# Sequei_board2.net
KiCad netlist of a schematic drawn in EAGLE
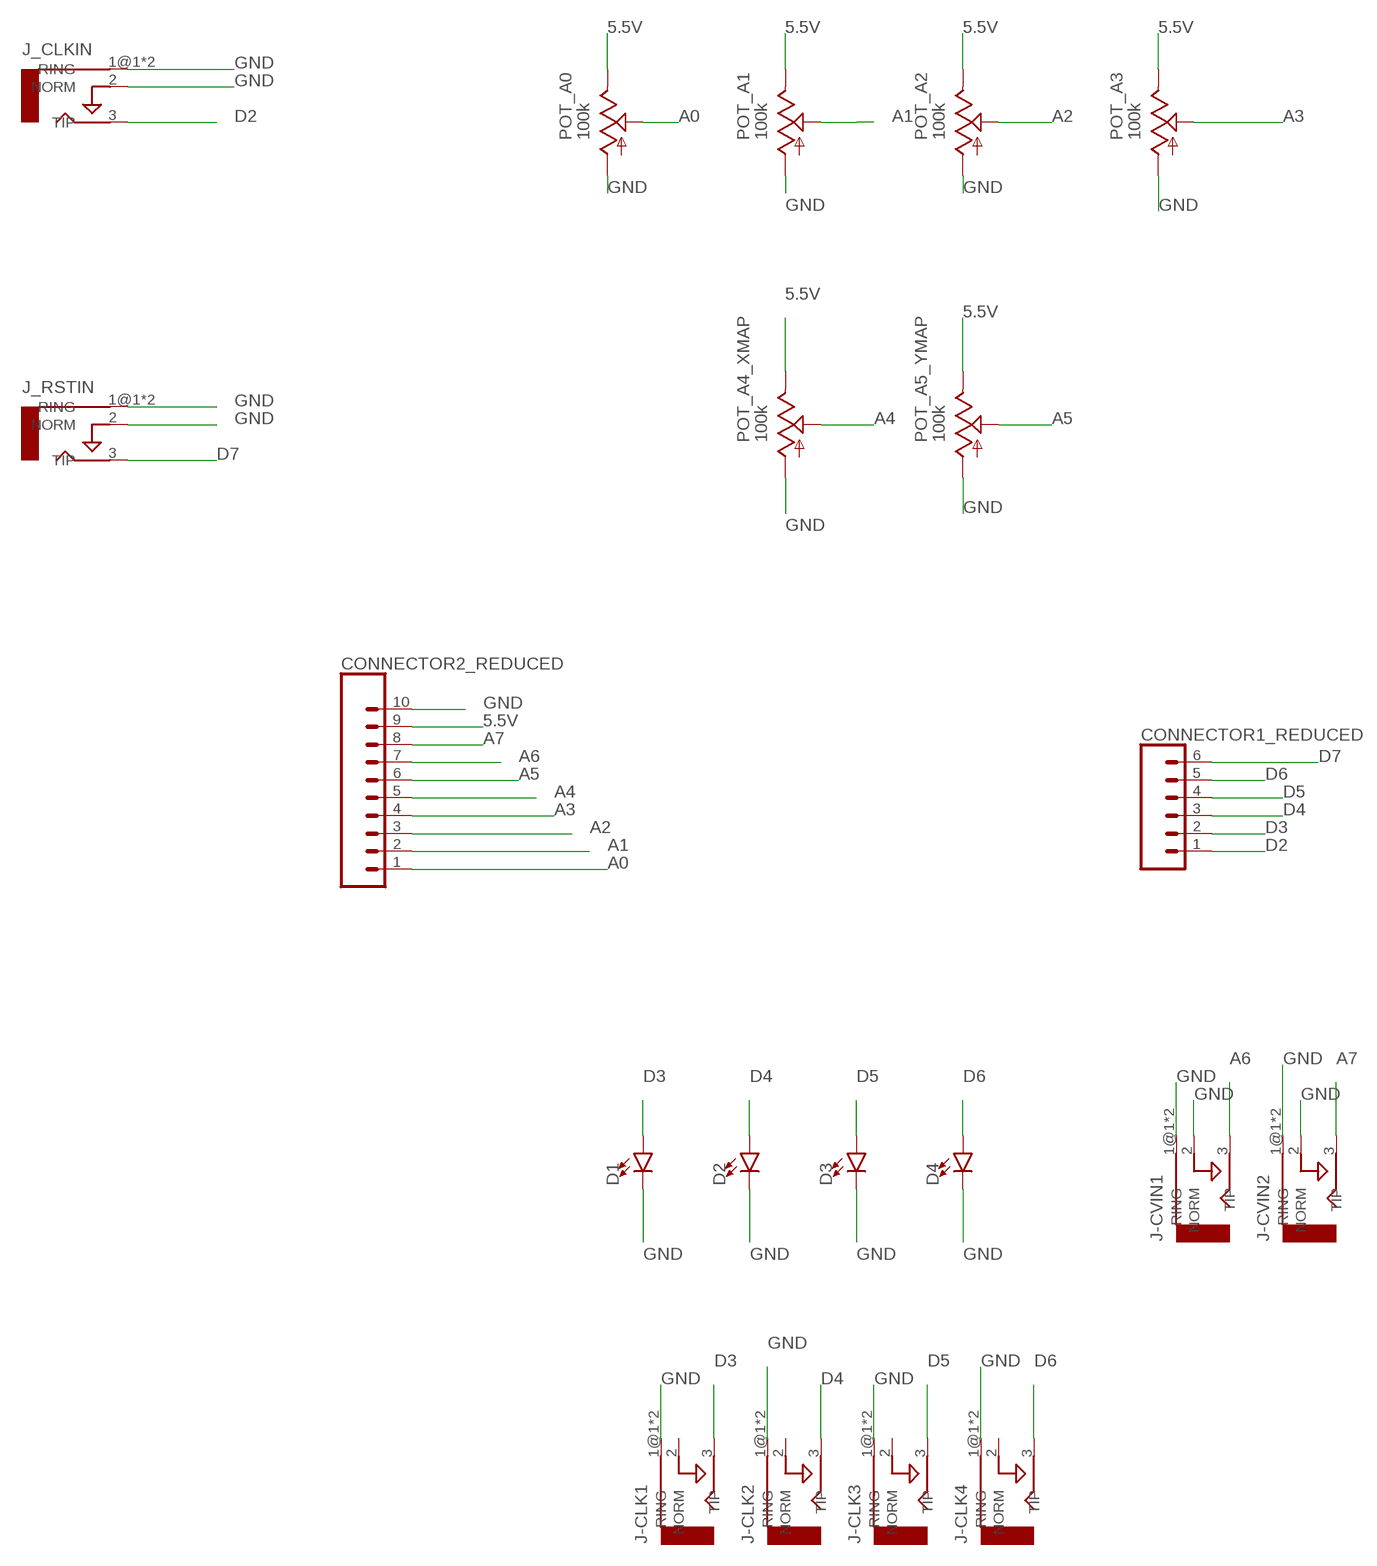
[diagram p0: schematic, sheet 1]

(export (version "E")
  (design (tool "Eeschema 10.0.6"))
  (components
    (comp (ref "CONNECTOR1_REDUCED")
      (value "CONN_06LONGPADS")
      (footprint "eagle-import:1X06_LONGPADS")
      (libsource (lib "eagle-import") (part "CONN_06LONGPADS"))
    )
    (comp (ref "CONNECTOR2_REDUCED")
      (value "CONN_10_LONGPADS10_LONGPADS")
      (footprint "eagle-import:1X10_LONGPADS")
      (libsource (lib "eagle-import") (part "CONN_10_LONGPADS10_LONGPADS"))
    )
    (comp (ref "D1")
      (value "LED-3MM-NO_SILK")
      (footprint "eagle-import:LED_3MM-NS")
      (libsource (lib "eagle-import") (part "LED-3MM-NO_SILK"))
    )
    (comp (ref "D2")
      (value "LED-3MM-NO_SILK")
      (footprint "eagle-import:LED_3MM-NS")
      (libsource (lib "eagle-import") (part "LED-3MM-NO_SILK"))
    )
    (comp (ref "D3")
      (value "LED-3MM-NO_SILK")
      (footprint "eagle-import:LED_3MM-NS")
      (libsource (lib "eagle-import") (part "LED-3MM-NO_SILK"))
    )
    (comp (ref "D4")
      (value "LED-3MM-NO_SILK")
      (footprint "eagle-import:LED_3MM-NS")
      (libsource (lib "eagle-import") (part "LED-3MM-NO_SILK"))
    )
    (comp (ref "J-CLK1")
      (value "AUDIO-JACKERTHENVAR")
      (footprint "eagle-import:ERTHENVAR-JACK")
      (libsource (lib "eagle-import") (part "AUDIO-JACKERTHENVAR"))
    )
    (comp (ref "J-CLK2")
      (value "AUDIO-JACKERTHENVAR")
      (footprint "eagle-import:ERTHENVAR-JACK")
      (libsource (lib "eagle-import") (part "AUDIO-JACKERTHENVAR"))
    )
    (comp (ref "J-CLK3")
      (value "AUDIO-JACKERTHENVAR")
      (footprint "eagle-import:ERTHENVAR-JACK")
      (libsource (lib "eagle-import") (part "AUDIO-JACKERTHENVAR"))
    )
    (comp (ref "J-CLK4")
      (value "AUDIO-JACKERTHENVAR")
      (footprint "eagle-import:ERTHENVAR-JACK")
      (libsource (lib "eagle-import") (part "AUDIO-JACKERTHENVAR"))
    )
    (comp (ref "J-CVIN1")
      (value "AUDIO-JACKERTHENVAR")
      (footprint "eagle-import:ERTHENVAR-JACK")
      (libsource (lib "eagle-import") (part "AUDIO-JACKERTHENVAR"))
    )
    (comp (ref "J-CVIN2")
      (value "AUDIO-JACKERTHENVAR")
      (footprint "eagle-import:ERTHENVAR-JACK")
      (libsource (lib "eagle-import") (part "AUDIO-JACKERTHENVAR"))
    )
    (comp (ref "J_CLKIN")
      (value "AUDIO-JACKERTHENVAR")
      (footprint "eagle-import:ERTHENVAR-JACK")
      (libsource (lib "eagle-import") (part "AUDIO-JACKERTHENVAR"))
    )
    (comp (ref "J_RSTIN")
      (value "AUDIO-JACKERTHENVAR")
      (footprint "eagle-import:ERTHENVAR-JACK")
      (libsource (lib "eagle-import") (part "AUDIO-JACKERTHENVAR"))
    )
    (comp (ref "POT_A0")
      (value "100k")
      (footprint "eagle-import:9MM_SNAP-IN_POT")
      (libsource (lib "eagle-import") (part "9MM_SNAP-IN_POT_"))
    )
    (comp (ref "POT_A1")
      (value "100k")
      (footprint "eagle-import:9MM_SNAP-IN_POT")
      (libsource (lib "eagle-import") (part "9MM_SNAP-IN_POT_"))
    )
    (comp (ref "POT_A2")
      (value "100k")
      (footprint "eagle-import:9MM_SNAP-IN_POT")
      (libsource (lib "eagle-import") (part "9MM_SNAP-IN_POT_"))
    )
    (comp (ref "POT_A3")
      (value "100k")
      (footprint "eagle-import:9MM_SNAP-IN_POT")
      (libsource (lib "eagle-import") (part "9MM_SNAP-IN_POT_"))
    )
    (comp (ref "POT_A4_XMAP")
      (value "100k")
      (footprint "eagle-import:9MM_SNAP-IN_POT")
      (libsource (lib "eagle-import") (part "9MM_SNAP-IN_POT_"))
    )
    (comp (ref "POT_A5_YMAP")
      (value "100k")
      (footprint "eagle-import:9MM_SNAP-IN_POT")
      (libsource (lib "eagle-import") (part "9MM_SNAP-IN_POT_"))
    )
  )
  (nets
    (net (code "1") (name "/5.5V") (class "Default")
      (node (ref "CONNECTOR2_REDUCED") (pin "9") (pinfunction "9_9") (pintype "passive"))
      (node (ref "POT_A0") (pin "3") (pinfunction "E_3") (pintype "passive"))
      (node (ref "POT_A1") (pin "3") (pinfunction "E_3") (pintype "passive"))
      (node (ref "POT_A2") (pin "3") (pinfunction "E_3") (pintype "passive"))
      (node (ref "POT_A3") (pin "3") (pinfunction "E_3") (pintype "passive"))
      (node (ref "POT_A4_XMAP") (pin "3") (pinfunction "E_3") (pintype "passive"))
      (node (ref "POT_A5_YMAP") (pin "3") (pinfunction "E_3") (pintype "passive"))
    )
    (net (code "2") (name "/A0") (class "Default")
      (node (ref "CONNECTOR2_REDUCED") (pin "1") (pinfunction "1_1") (pintype "passive"))
      (node (ref "POT_A0") (pin "2") (pinfunction "S_2") (pintype "passive"))
    )
    (net (code "3") (name "/A1") (class "Default")
      (node (ref "CONNECTOR2_REDUCED") (pin "2") (pinfunction "2_2") (pintype "passive"))
      (node (ref "POT_A1") (pin "2") (pinfunction "S_2") (pintype "passive"))
    )
    (net (code "4") (name "/A2") (class "Default")
      (node (ref "CONNECTOR2_REDUCED") (pin "3") (pinfunction "3_3") (pintype "passive"))
      (node (ref "POT_A2") (pin "2") (pinfunction "S_2") (pintype "passive"))
    )
    (net (code "5") (name "/A3") (class "Default")
      (node (ref "CONNECTOR2_REDUCED") (pin "4") (pinfunction "4_4") (pintype "passive"))
      (node (ref "POT_A3") (pin "2") (pinfunction "S_2") (pintype "passive"))
    )
    (net (code "6") (name "/A4") (class "Default")
      (node (ref "CONNECTOR2_REDUCED") (pin "5") (pinfunction "5_5") (pintype "passive"))
      (node (ref "POT_A4_XMAP") (pin "2") (pinfunction "S_2") (pintype "passive"))
    )
    (net (code "7") (name "/A5") (class "Default")
      (node (ref "CONNECTOR2_REDUCED") (pin "6") (pinfunction "6_6") (pintype "passive"))
      (node (ref "POT_A5_YMAP") (pin "2") (pinfunction "S_2") (pintype "passive"))
    )
    (net (code "8") (name "/A6") (class "Default")
      (node (ref "CONNECTOR2_REDUCED") (pin "7") (pinfunction "7_7") (pintype "passive"))
      (node (ref "J-CVIN1") (pin "3") (pinfunction "TIP_3") (pintype "bidirectional"))
    )
    (net (code "9") (name "/A7") (class "Default")
      (node (ref "CONNECTOR2_REDUCED") (pin "8") (pinfunction "8_8") (pintype "passive"))
      (node (ref "J-CVIN2") (pin "3") (pinfunction "TIP_3") (pintype "bidirectional"))
    )
    (net (code "10") (name "/D2") (class "Default")
      (node (ref "CONNECTOR1_REDUCED") (pin "1") (pinfunction "1_1") (pintype "passive"))
      (node (ref "J_CLKIN") (pin "3") (pinfunction "TIP_3") (pintype "bidirectional"))
    )
    (net (code "11") (name "/D3") (class "Default")
      (node (ref "CONNECTOR1_REDUCED") (pin "2") (pinfunction "2_2") (pintype "passive"))
      (node (ref "D1") (pin "A") (pinfunction "A_A") (pintype "passive"))
      (node (ref "J-CLK1") (pin "3") (pinfunction "TIP_3") (pintype "bidirectional"))
    )
    (net (code "12") (name "/D4") (class "Default")
      (node (ref "CONNECTOR1_REDUCED") (pin "3") (pinfunction "3_3") (pintype "passive"))
      (node (ref "D2") (pin "A") (pinfunction "A_A") (pintype "passive"))
      (node (ref "J-CLK2") (pin "3") (pinfunction "TIP_3") (pintype "bidirectional"))
    )
    (net (code "13") (name "/D5") (class "Default")
      (node (ref "CONNECTOR1_REDUCED") (pin "4") (pinfunction "4_4") (pintype "passive"))
      (node (ref "D3") (pin "A") (pinfunction "A_A") (pintype "passive"))
      (node (ref "J-CLK3") (pin "3") (pinfunction "TIP_3") (pintype "bidirectional"))
    )
    (net (code "14") (name "/D6") (class "Default")
      (node (ref "CONNECTOR1_REDUCED") (pin "5") (pinfunction "5_5") (pintype "passive"))
      (node (ref "D4") (pin "A") (pinfunction "A_A") (pintype "passive"))
      (node (ref "J-CLK4") (pin "3") (pinfunction "TIP_3") (pintype "bidirectional"))
    )
    (net (code "15") (name "/D7") (class "Default")
      (node (ref "CONNECTOR1_REDUCED") (pin "6") (pinfunction "6_6") (pintype "passive"))
      (node (ref "J_RSTIN") (pin "3") (pinfunction "TIP_3") (pintype "bidirectional"))
    )
    (net (code "16") (name "/GND") (class "Default")
      (node (ref "CONNECTOR2_REDUCED") (pin "10") (pinfunction "10_10") (pintype "passive"))
      (node (ref "D1") (pin "K") (pinfunction "C_K") (pintype "passive"))
      (node (ref "D2") (pin "K") (pinfunction "C_K") (pintype "passive"))
      (node (ref "D3") (pin "K") (pinfunction "C_K") (pintype "passive"))
      (node (ref "D4") (pin "K") (pinfunction "C_K") (pintype "passive"))
      (node (ref "J-CLK1") (pin "1@1") (pinfunction "RING_1@1") (pintype "bidirectional"))
      (node (ref "J-CLK1") (pin "1@2") (pinfunction "RING_1@2") (pintype "bidirectional"))
      (node (ref "J-CLK2") (pin "1@1") (pinfunction "RING_1@1") (pintype "bidirectional"))
      (node (ref "J-CLK2") (pin "1@2") (pinfunction "RING_1@2") (pintype "bidirectional"))
      (node (ref "J-CLK3") (pin "1@1") (pinfunction "RING_1@1") (pintype "bidirectional"))
      (node (ref "J-CLK3") (pin "1@2") (pinfunction "RING_1@2") (pintype "bidirectional"))
      (node (ref "J-CLK4") (pin "1@1") (pinfunction "RING_1@1") (pintype "bidirectional"))
      (node (ref "J-CLK4") (pin "1@2") (pinfunction "RING_1@2") (pintype "bidirectional"))
      (node (ref "J-CVIN1") (pin "1@1") (pinfunction "RING_1@1") (pintype "bidirectional"))
      (node (ref "J-CVIN1") (pin "1@2") (pinfunction "RING_1@2") (pintype "bidirectional"))
      (node (ref "J-CVIN1") (pin "2") (pinfunction "NORM_2") (pintype "bidirectional"))
      (node (ref "J-CVIN2") (pin "1@1") (pinfunction "RING_1@1") (pintype "bidirectional"))
      (node (ref "J-CVIN2") (pin "1@2") (pinfunction "RING_1@2") (pintype "bidirectional"))
      (node (ref "J-CVIN2") (pin "2") (pinfunction "NORM_2") (pintype "bidirectional"))
      (node (ref "J_CLKIN") (pin "1@1") (pinfunction "RING_1@1") (pintype "bidirectional"))
      (node (ref "J_CLKIN") (pin "1@2") (pinfunction "RING_1@2") (pintype "bidirectional"))
      (node (ref "J_CLKIN") (pin "2") (pinfunction "NORM_2") (pintype "bidirectional"))
      (node (ref "J_RSTIN") (pin "1@1") (pinfunction "RING_1@1") (pintype "bidirectional"))
      (node (ref "J_RSTIN") (pin "1@2") (pinfunction "RING_1@2") (pintype "bidirectional"))
      (node (ref "J_RSTIN") (pin "2") (pinfunction "NORM_2") (pintype "bidirectional"))
      (node (ref "POT_A0") (pin "1") (pinfunction "A_1") (pintype "passive"))
      (node (ref "POT_A1") (pin "1") (pinfunction "A_1") (pintype "passive"))
      (node (ref "POT_A2") (pin "1") (pinfunction "A_1") (pintype "passive"))
      (node (ref "POT_A3") (pin "1") (pinfunction "A_1") (pintype "passive"))
      (node (ref "POT_A4_XMAP") (pin "1") (pinfunction "A_1") (pintype "passive"))
      (node (ref "POT_A5_YMAP") (pin "1") (pinfunction "A_1") (pintype "passive"))
    )
    (net (code "17") (name "unconnected-(J-CLK1-NORM-Pad2)") (class "Default")
      (node (ref "J-CLK1") (pin "2") (pinfunction "NORM_2") (pintype "bidirectional"))
    )
    (net (code "18") (name "unconnected-(J-CLK2-NORM-Pad2)") (class "Default")
      (node (ref "J-CLK2") (pin "2") (pinfunction "NORM_2") (pintype "bidirectional"))
    )
    (net (code "19") (name "unconnected-(J-CLK3-NORM-Pad2)") (class "Default")
      (node (ref "J-CLK3") (pin "2") (pinfunction "NORM_2") (pintype "bidirectional"))
    )
    (net (code "20") (name "unconnected-(J-CLK4-NORM-Pad2)") (class "Default")
      (node (ref "J-CLK4") (pin "2") (pinfunction "NORM_2") (pintype "bidirectional"))
    )
  )
)
